# tree.net
KiCad netlist of a schematic drawn in EAGLE
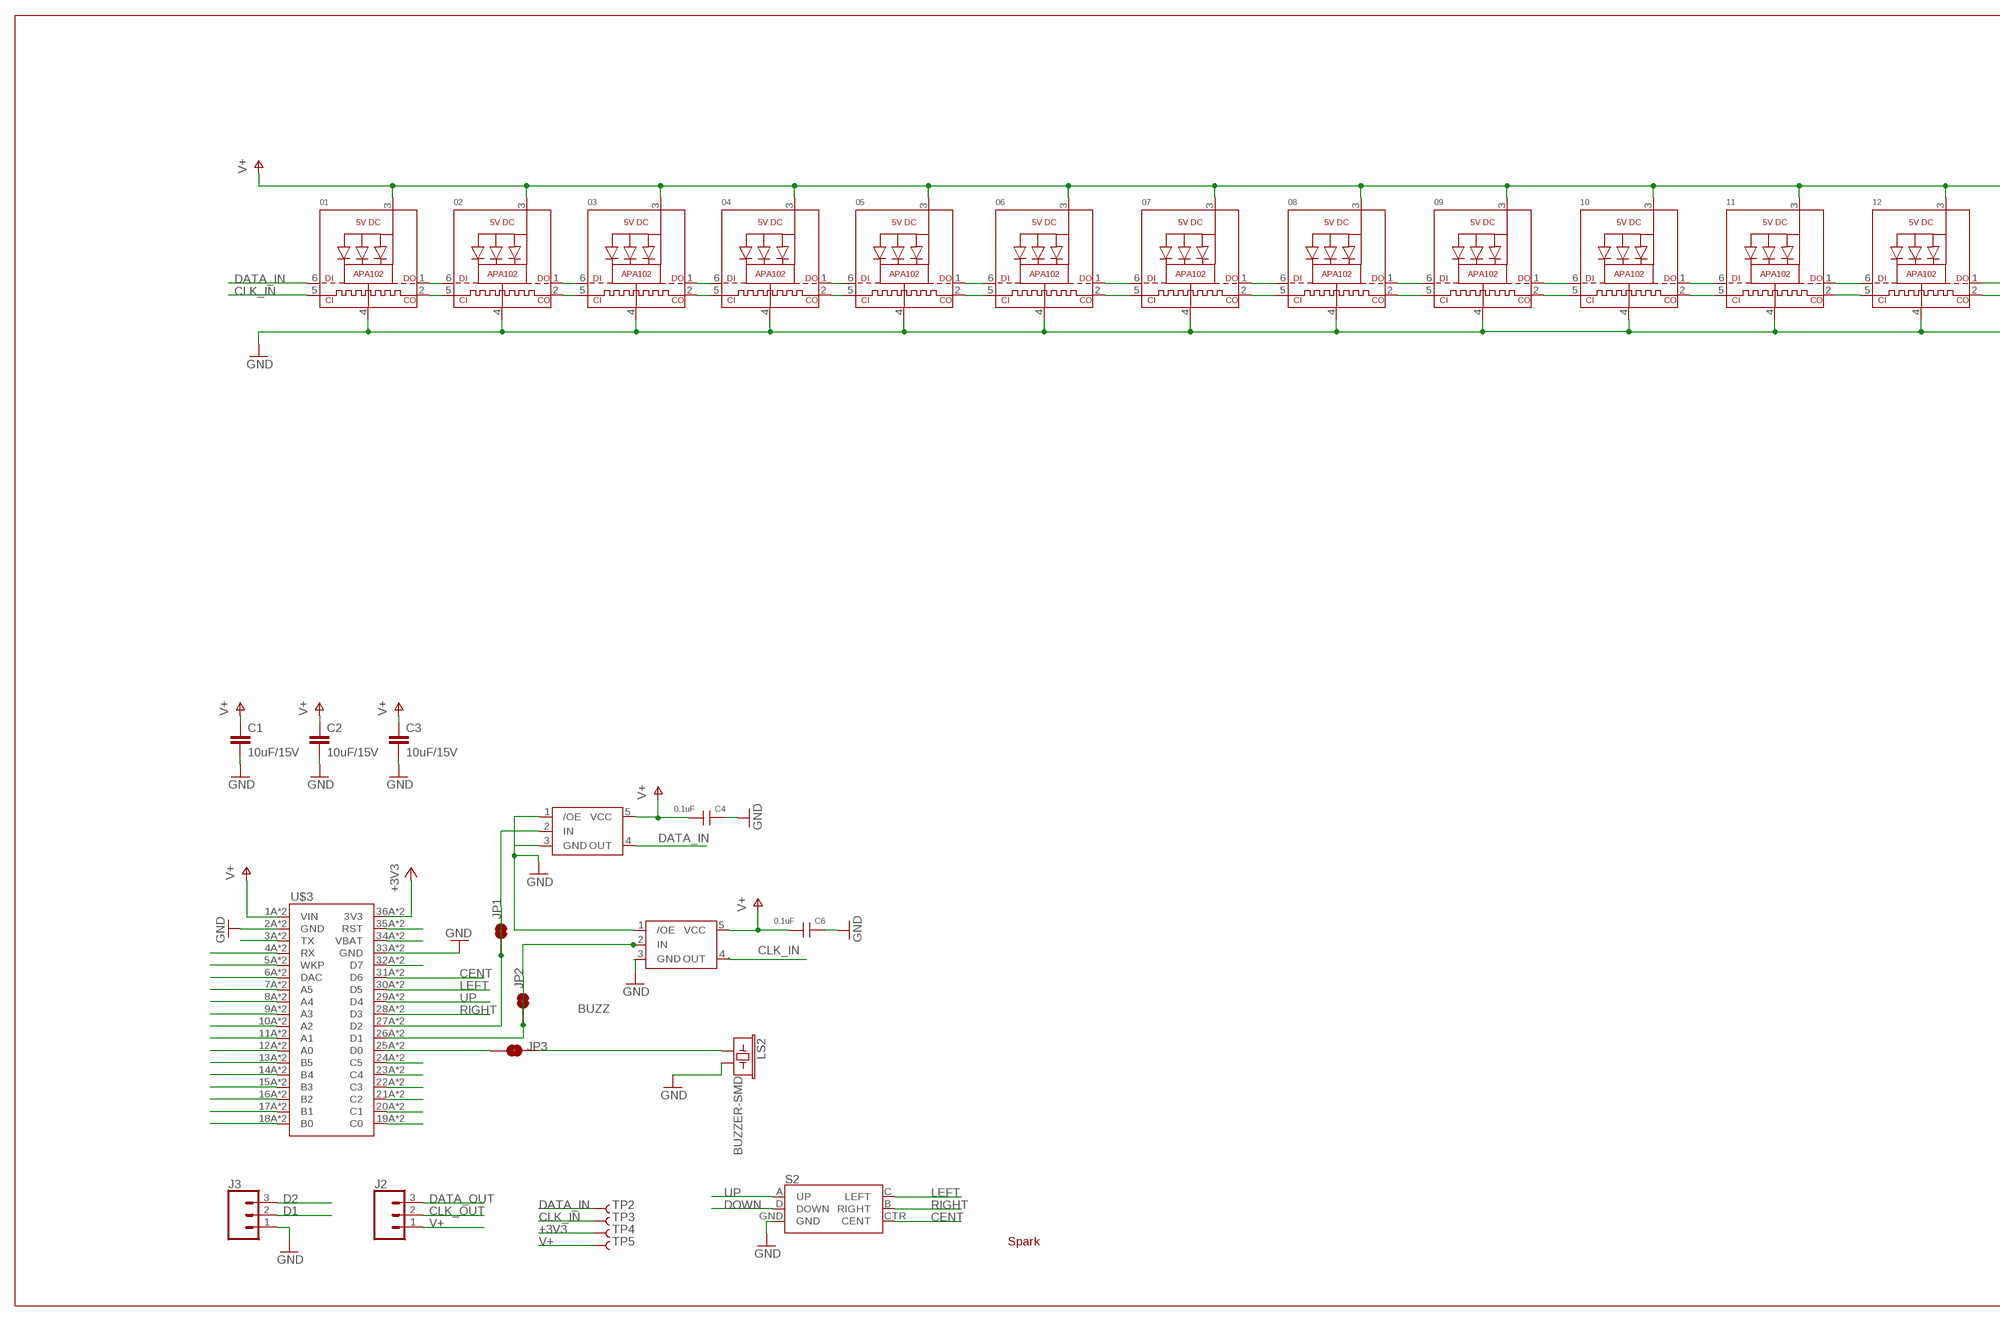
[diagram p0: schematic, sheet 1, part 1 of 3]
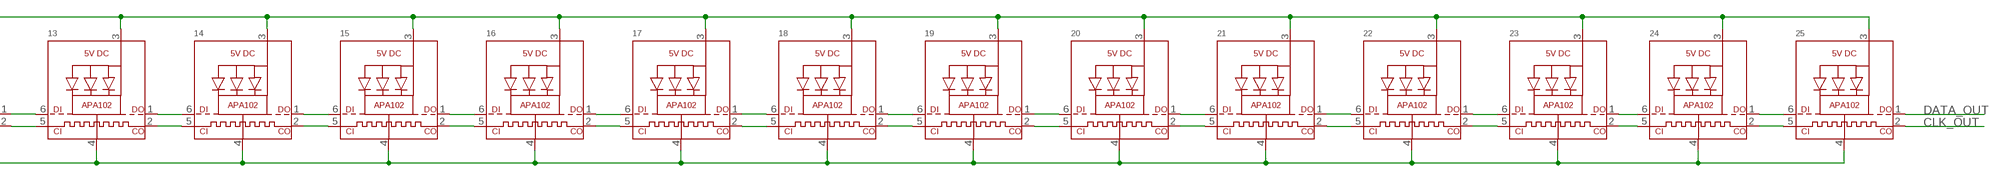
[diagram p1: schematic, sheet 1, part 2 of 3]
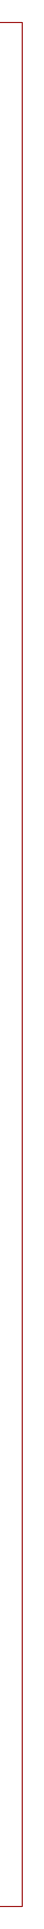
[diagram p2: schematic, sheet 1, part 3 of 3]

(export (version "E")
  (design (tool "Eeschema 10.0.6"))
  (components
    (comp (ref "01")
      (value "APA1022020")
      (footprint "eagle-import:APA102_2020")
      (libsource (lib "eagle-import") (part "APA1022020"))
    )
    (comp (ref "02")
      (value "APA1022020")
      (footprint "eagle-import:APA102_2020")
      (libsource (lib "eagle-import") (part "APA1022020"))
    )
    (comp (ref "03")
      (value "APA1022020")
      (footprint "eagle-import:APA102_2020")
      (libsource (lib "eagle-import") (part "APA1022020"))
    )
    (comp (ref "04")
      (value "APA1022020")
      (footprint "eagle-import:APA102_2020")
      (libsource (lib "eagle-import") (part "APA1022020"))
    )
    (comp (ref "05")
      (value "APA1022020")
      (footprint "eagle-import:APA102_2020")
      (libsource (lib "eagle-import") (part "APA1022020"))
    )
    (comp (ref "06")
      (value "APA1022020")
      (footprint "eagle-import:APA102_2020")
      (libsource (lib "eagle-import") (part "APA1022020"))
    )
    (comp (ref "07")
      (value "APA1022020")
      (footprint "eagle-import:APA102_2020")
      (libsource (lib "eagle-import") (part "APA1022020"))
    )
    (comp (ref "08")
      (value "APA1022020")
      (footprint "eagle-import:APA102_2020")
      (libsource (lib "eagle-import") (part "APA1022020"))
    )
    (comp (ref "09")
      (value "APA1022020")
      (footprint "eagle-import:APA102_2020")
      (libsource (lib "eagle-import") (part "APA1022020"))
    )
    (comp (ref "10")
      (value "APA1022020")
      (footprint "eagle-import:APA102_2020")
      (libsource (lib "eagle-import") (part "APA1022020"))
    )
    (comp (ref "11")
      (value "APA1022020")
      (footprint "eagle-import:APA102_2020")
      (libsource (lib "eagle-import") (part "APA1022020"))
    )
    (comp (ref "12")
      (value "APA1022020")
      (footprint "eagle-import:APA102_2020")
      (libsource (lib "eagle-import") (part "APA1022020"))
    )
    (comp (ref "13")
      (value "APA1022020")
      (footprint "eagle-import:APA102_2020")
      (libsource (lib "eagle-import") (part "APA1022020"))
    )
    (comp (ref "14")
      (value "APA1022020")
      (footprint "eagle-import:APA102_2020")
      (libsource (lib "eagle-import") (part "APA1022020"))
    )
    (comp (ref "15")
      (value "APA1022020")
      (footprint "eagle-import:APA102_2020")
      (libsource (lib "eagle-import") (part "APA1022020"))
    )
    (comp (ref "16")
      (value "APA1022020")
      (footprint "eagle-import:APA102_2020")
      (libsource (lib "eagle-import") (part "APA1022020"))
    )
    (comp (ref "17")
      (value "APA1022020")
      (footprint "eagle-import:APA102_2020")
      (libsource (lib "eagle-import") (part "APA1022020"))
    )
    (comp (ref "18")
      (value "APA1022020")
      (footprint "eagle-import:APA102_2020")
      (libsource (lib "eagle-import") (part "APA1022020"))
    )
    (comp (ref "19")
      (value "APA1022020")
      (footprint "eagle-import:APA102_2020")
      (libsource (lib "eagle-import") (part "APA1022020"))
    )
    (comp (ref "20")
      (value "APA1022020")
      (footprint "eagle-import:APA102_2020")
      (libsource (lib "eagle-import") (part "APA1022020"))
    )
    (comp (ref "21")
      (value "APA1022020")
      (footprint "eagle-import:APA102_2020")
      (libsource (lib "eagle-import") (part "APA1022020"))
    )
    (comp (ref "22")
      (value "APA1022020")
      (footprint "eagle-import:APA102_2020")
      (libsource (lib "eagle-import") (part "APA1022020"))
    )
    (comp (ref "23")
      (value "APA1022020")
      (footprint "eagle-import:APA102_2020")
      (libsource (lib "eagle-import") (part "APA1022020"))
    )
    (comp (ref "24")
      (value "APA1022020")
      (footprint "eagle-import:APA102_2020")
      (libsource (lib "eagle-import") (part "APA1022020"))
    )
    (comp (ref "25")
      (value "APA1022020")
      (footprint "eagle-import:APA102_2020")
      (libsource (lib "eagle-import") (part "APA1022020"))
    )
    (comp (ref "C1")
      (value "10uF/15V")
      (footprint "eagle-import:C0805K")
      (libsource (lib "eagle-import") (part "C-EUC0805K"))
    )
    (comp (ref "C2")
      (value "10uF/15V")
      (footprint "eagle-import:C0805K")
      (libsource (lib "eagle-import") (part "C-EUC0805K"))
    )
    (comp (ref "C3")
      (value "10uF/15V")
      (footprint "eagle-import:C0805K")
      (libsource (lib "eagle-import") (part "C-EUC0805K"))
    )
    (comp (ref "C4")
      (value "0.1uF")
      (footprint "eagle-import:C-0603A")
      (libsource (lib "eagle-import") (part "CAP0603A"))
    )
    (comp (ref "C6")
      (value "0.1uF")
      (footprint "eagle-import:C-0603A")
      (libsource (lib "eagle-import") (part "CAP0603A"))
    )
    (comp (ref "J2")
      (value "CONN_03")
      (footprint "eagle-import:1X03")
      (libsource (lib "eagle-import") (part "CONN_03"))
    )
    (comp (ref "J3")
      (value "CONN_03")
      (footprint "eagle-import:1X03")
      (libsource (lib "eagle-import") (part "CONN_03"))
    )
    (comp (ref "JP1")
      (value "JUMPER-SMT_2_NC_TRACE_NO-SILK")
      (footprint "eagle-import:SMT-JUMPER_2_NC_TRACE_NO-SILK")
      (libsource (lib "eagle-import") (part "JUMPER-SMT_2_NC_TRACE_NO-SILK"))
    )
    (comp (ref "JP2")
      (value "JUMPER-SMT_2_NC_TRACE_NO-SILK")
      (footprint "eagle-import:SMT-JUMPER_2_NC_TRACE_NO-SILK")
      (libsource (lib "eagle-import") (part "JUMPER-SMT_2_NC_TRACE_NO-SILK"))
    )
    (comp (ref "JP3")
      (value "JUMPER-SMT_2_NC_TRACE_NO-SILK")
      (footprint "eagle-import:SMT-JUMPER_2_NC_TRACE_NO-SILK")
      (libsource (lib "eagle-import") (part "JUMPER-SMT_2_NC_TRACE_NO-SILK"))
    )
    (comp (ref "LS2")
      (value "BUZZER-SMD")
      (footprint "eagle-import:BUZZER-CCV")
      (libsource (lib "eagle-import") (part "BUZZER-SMD"))
    )
    (comp (ref "S2")
      (value "JOYSTICK_MINI")
      (footprint "eagle-import:JOYSTICK_MINI")
      (libsource (lib "eagle-import") (part "JOYSTICK_MINI"))
    )
    (comp (ref "TP2")
      (value "TEST-POINT3")
      (footprint "eagle-import:PAD.03X.03")
      (libsource (lib "eagle-import") (part "TEST-POINT3"))
    )
    (comp (ref "TP3")
      (value "TEST-POINT3")
      (footprint "eagle-import:PAD.03X.03")
      (libsource (lib "eagle-import") (part "TEST-POINT3"))
    )
    (comp (ref "TP4")
      (value "TEST-POINT3")
      (footprint "eagle-import:PAD.03X.03")
      (libsource (lib "eagle-import") (part "TEST-POINT3"))
    )
    (comp (ref "TP5")
      (value "TEST-POINT3")
      (footprint "eagle-import:PAD.03X.03")
      (libsource (lib "eagle-import") (part "TEST-POINT3"))
    )
    (comp (ref "U$1")
      (value "SPARK_LOGO")
      (footprint "eagle-import:SPARK_LOGO_TSTOP")
      (libsource (lib "eagle-import") (part "SPARK_LOGO"))
    )
    (comp (ref "U$3")
      (value "ELECTRON_SMT")
      (footprint "eagle-import:ELECTRON_SMT")
      (libsource (lib "eagle-import") (part "ELECTRON_SMT"))
    )
    (comp (ref "U1")
      (value "NL17SZ125")
      (footprint "eagle-import:SOT-353")
      (libsource (lib "eagle-import") (part "NL17SZ125"))
    )
    (comp (ref "U2")
      (value "NL17SZ125")
      (footprint "eagle-import:SOT-353")
      (libsource (lib "eagle-import") (part "NL17SZ125"))
    )
  )
  (nets
    (net (code "1") (name "+3V3") (class "Default")
      (node (ref "TP4") (pin "P$1") (pinfunction "1_P$1") (pintype "bidirectional"))
      (node (ref "U$3") (pin "36A") (pinfunction "3V3_36A") (pintype "power_in"))
      (node (ref "U$3") (pin "36B") (pinfunction "3V3_36B") (pintype "power_in"))
    )
    (net (code "2") (name "/BUZZ") (class "Default")
      (node (ref "JP3") (pin "1") (pinfunction "1_1") (pintype "passive"))
      (node (ref "U$3") (pin "25A") (pinfunction "D0_25A") (pintype "bidirectional"))
      (node (ref "U$3") (pin "25B") (pinfunction "D0_25B") (pintype "bidirectional"))
    )
    (net (code "3") (name "/CENT") (class "Default")
      (node (ref "S2") (pin "CTR") (pinfunction "CENT_CTR") (pintype "bidirectional"))
      (node (ref "U$3") (pin "31A") (pinfunction "D6_31A") (pintype "bidirectional"))
      (node (ref "U$3") (pin "31B") (pinfunction "D6_31B") (pintype "bidirectional"))
    )
    (net (code "4") (name "/CLK_IN") (class "Default")
      (node (ref "01") (pin "5") (pinfunction "CKI_5") (pintype "input"))
      (node (ref "TP3") (pin "P$1") (pinfunction "1_P$1") (pintype "bidirectional"))
      (node (ref "U2") (pin "4") (pinfunction "OUT_4") (pintype "bidirectional"))
    )
    (net (code "5") (name "/CLK_OUT") (class "Default")
      (node (ref "25") (pin "2") (pinfunction "CKO_2") (pintype "output"))
      (node (ref "J2") (pin "2") (pinfunction "2_2") (pintype "passive"))
    )
    (net (code "6") (name "/D1") (class "Default")
      (node (ref "J3") (pin "2") (pinfunction "2_2") (pintype "passive"))
      (node (ref "JP2") (pin "1") (pinfunction "1_1") (pintype "passive"))
      (node (ref "JP2") (pin "2") (pinfunction "2_2") (pintype "passive"))
      (node (ref "U$3") (pin "26A") (pinfunction "D1_26A") (pintype "bidirectional"))
      (node (ref "U$3") (pin "26B") (pinfunction "D1_26B") (pintype "bidirectional"))
      (node (ref "U2") (pin "2") (pinfunction "IN_2") (pintype "bidirectional"))
    )
    (net (code "7") (name "/D2") (class "Default")
      (node (ref "J3") (pin "3") (pinfunction "3_3") (pintype "passive"))
      (node (ref "JP1") (pin "1") (pinfunction "1_1") (pintype "passive"))
      (node (ref "JP1") (pin "2") (pinfunction "2_2") (pintype "passive"))
      (node (ref "U$3") (pin "27A") (pinfunction "D2_27A") (pintype "bidirectional"))
      (node (ref "U$3") (pin "27B") (pinfunction "D2_27B") (pintype "bidirectional"))
      (node (ref "U1") (pin "2") (pinfunction "IN_2") (pintype "bidirectional"))
    )
    (net (code "8") (name "/DATA_IN") (class "Default")
      (node (ref "01") (pin "6") (pinfunction "DI_6") (pintype "input"))
      (node (ref "TP2") (pin "P$1") (pinfunction "1_P$1") (pintype "bidirectional"))
      (node (ref "U1") (pin "4") (pinfunction "OUT_4") (pintype "bidirectional"))
    )
    (net (code "9") (name "/DATA_OUT") (class "Default")
      (node (ref "25") (pin "1") (pinfunction "DO_1") (pintype "output"))
      (node (ref "J2") (pin "3") (pinfunction "3_3") (pintype "passive"))
    )
    (net (code "10") (name "/DOWN") (class "Default")
      (node (ref "S2") (pin "D") (pinfunction "DOWN_D") (pintype "bidirectional"))
      (node (ref "U$3") (pin "12A") (pinfunction "A0_12A") (pintype "bidirectional"))
      (node (ref "U$3") (pin "12B") (pinfunction "A0_12B") (pintype "bidirectional"))
    )
    (net (code "11") (name "/LEFT") (class "Default")
      (node (ref "S2") (pin "C") (pinfunction "LEFT_C") (pintype "bidirectional"))
      (node (ref "U$3") (pin "30A") (pinfunction "D5_30A") (pintype "bidirectional"))
      (node (ref "U$3") (pin "30B") (pinfunction "D5_30B") (pintype "bidirectional"))
    )
    (net (code "12") (name "/RIGHT") (class "Default")
      (node (ref "S2") (pin "B") (pinfunction "RIGHT_B") (pintype "bidirectional"))
      (node (ref "U$3") (pin "28A") (pinfunction "D3_28A") (pintype "bidirectional"))
      (node (ref "U$3") (pin "28B") (pinfunction "D3_28B") (pintype "bidirectional"))
    )
    (net (code "13") (name "/UP") (class "Default")
      (node (ref "S2") (pin "A") (pinfunction "UP_A") (pintype "bidirectional"))
      (node (ref "U$3") (pin "29A") (pinfunction "D4_29A") (pintype "bidirectional"))
      (node (ref "U$3") (pin "29B") (pinfunction "D4_29B") (pintype "bidirectional"))
    )
    (net (code "14") (name "GND") (class "Default")
      (node (ref "01") (pin "4") (pinfunction "GND_4") (pintype "power_in"))
      (node (ref "02") (pin "4") (pinfunction "GND_4") (pintype "power_in"))
      (node (ref "03") (pin "4") (pinfunction "GND_4") (pintype "power_in"))
      (node (ref "04") (pin "4") (pinfunction "GND_4") (pintype "power_in"))
      (node (ref "05") (pin "4") (pinfunction "GND_4") (pintype "power_in"))
      (node (ref "06") (pin "4") (pinfunction "GND_4") (pintype "power_in"))
      (node (ref "07") (pin "4") (pinfunction "GND_4") (pintype "power_in"))
      (node (ref "08") (pin "4") (pinfunction "GND_4") (pintype "power_in"))
      (node (ref "09") (pin "4") (pinfunction "GND_4") (pintype "power_in"))
      (node (ref "10") (pin "4") (pinfunction "GND_4") (pintype "power_in"))
      (node (ref "11") (pin "4") (pinfunction "GND_4") (pintype "power_in"))
      (node (ref "12") (pin "4") (pinfunction "GND_4") (pintype "power_in"))
      (node (ref "13") (pin "4") (pinfunction "GND_4") (pintype "power_in"))
      (node (ref "14") (pin "4") (pinfunction "GND_4") (pintype "power_in"))
      (node (ref "15") (pin "4") (pinfunction "GND_4") (pintype "power_in"))
      (node (ref "16") (pin "4") (pinfunction "GND_4") (pintype "power_in"))
      (node (ref "17") (pin "4") (pinfunction "GND_4") (pintype "power_in"))
      (node (ref "18") (pin "4") (pinfunction "GND_4") (pintype "power_in"))
      (node (ref "19") (pin "4") (pinfunction "GND_4") (pintype "power_in"))
      (node (ref "20") (pin "4") (pinfunction "GND_4") (pintype "power_in"))
      (node (ref "21") (pin "4") (pinfunction "GND_4") (pintype "power_in"))
      (node (ref "22") (pin "4") (pinfunction "GND_4") (pintype "power_in"))
      (node (ref "23") (pin "4") (pinfunction "GND_4") (pintype "power_in"))
      (node (ref "24") (pin "4") (pinfunction "GND_4") (pintype "power_in"))
      (node (ref "25") (pin "4") (pinfunction "GND_4") (pintype "power_in"))
      (node (ref "C1") (pin "2") (pinfunction "2_2") (pintype "passive"))
      (node (ref "C2") (pin "2") (pinfunction "2_2") (pintype "passive"))
      (node (ref "C3") (pin "2") (pinfunction "2_2") (pintype "passive"))
      (node (ref "C4") (pin "2") (pinfunction "2_2") (pintype "bidirectional"))
      (node (ref "C6") (pin "2") (pinfunction "2_2") (pintype "bidirectional"))
      (node (ref "J3") (pin "1") (pinfunction "1_1") (pintype "passive"))
      (node (ref "LS2") (pin "-") (pinfunction "2_-") (pintype "passive"))
      (node (ref "S2") (pin "GND") (pinfunction "GND_GND") (pintype "bidirectional"))
      (node (ref "U$3") (pin "2A") (pinfunction "GND_2A") (pintype "power_in"))
      (node (ref "U$3") (pin "2B") (pinfunction "GND_2B") (pintype "power_in"))
      (node (ref "U$3") (pin "33A") (pinfunction "GND_33A") (pintype "power_in"))
      (node (ref "U$3") (pin "33B") (pinfunction "GND_33B") (pintype "power_in"))
      (node (ref "U1") (pin "1") (pinfunction "/OE_1") (pintype "bidirectional"))
      (node (ref "U1") (pin "3") (pinfunction "GND_3") (pintype "bidirectional"))
      (node (ref "U2") (pin "1") (pinfunction "/OE_1") (pintype "bidirectional"))
      (node (ref "U2") (pin "3") (pinfunction "GND_3") (pintype "bidirectional"))
    )
    (net (code "15") (name "Net-(01-CKO)") (class "Default")
      (node (ref "01") (pin "2") (pinfunction "CKO_2") (pintype "output"))
      (node (ref "02") (pin "5") (pinfunction "CKI_5") (pintype "input"))
    )
    (net (code "16") (name "Net-(01-DO)") (class "Default")
      (node (ref "01") (pin "1") (pinfunction "DO_1") (pintype "output"))
      (node (ref "02") (pin "6") (pinfunction "DI_6") (pintype "input"))
    )
    (net (code "17") (name "Net-(02-CKO)") (class "Default")
      (node (ref "02") (pin "2") (pinfunction "CKO_2") (pintype "output"))
      (node (ref "03") (pin "5") (pinfunction "CKI_5") (pintype "input"))
    )
    (net (code "18") (name "Net-(02-DO)") (class "Default")
      (node (ref "02") (pin "1") (pinfunction "DO_1") (pintype "output"))
      (node (ref "03") (pin "6") (pinfunction "DI_6") (pintype "input"))
    )
    (net (code "19") (name "Net-(03-CKO)") (class "Default")
      (node (ref "03") (pin "2") (pinfunction "CKO_2") (pintype "output"))
      (node (ref "04") (pin "5") (pinfunction "CKI_5") (pintype "input"))
    )
    (net (code "20") (name "Net-(03-DO)") (class "Default")
      (node (ref "03") (pin "1") (pinfunction "DO_1") (pintype "output"))
      (node (ref "04") (pin "6") (pinfunction "DI_6") (pintype "input"))
    )
    (net (code "21") (name "Net-(04-CKO)") (class "Default")
      (node (ref "04") (pin "2") (pinfunction "CKO_2") (pintype "output"))
      (node (ref "05") (pin "5") (pinfunction "CKI_5") (pintype "input"))
    )
    (net (code "22") (name "Net-(04-DO)") (class "Default")
      (node (ref "04") (pin "1") (pinfunction "DO_1") (pintype "output"))
      (node (ref "05") (pin "6") (pinfunction "DI_6") (pintype "input"))
    )
    (net (code "23") (name "Net-(05-CKO)") (class "Default")
      (node (ref "05") (pin "2") (pinfunction "CKO_2") (pintype "output"))
      (node (ref "06") (pin "5") (pinfunction "CKI_5") (pintype "input"))
    )
    (net (code "24") (name "Net-(05-DO)") (class "Default")
      (node (ref "05") (pin "1") (pinfunction "DO_1") (pintype "output"))
      (node (ref "06") (pin "6") (pinfunction "DI_6") (pintype "input"))
    )
    (net (code "25") (name "Net-(06-CKO)") (class "Default")
      (node (ref "06") (pin "2") (pinfunction "CKO_2") (pintype "output"))
      (node (ref "07") (pin "5") (pinfunction "CKI_5") (pintype "input"))
    )
    (net (code "26") (name "Net-(06-DO)") (class "Default")
      (node (ref "06") (pin "1") (pinfunction "DO_1") (pintype "output"))
      (node (ref "07") (pin "6") (pinfunction "DI_6") (pintype "input"))
    )
    (net (code "27") (name "Net-(07-CKO)") (class "Default")
      (node (ref "07") (pin "2") (pinfunction "CKO_2") (pintype "output"))
      (node (ref "08") (pin "5") (pinfunction "CKI_5") (pintype "input"))
    )
    (net (code "28") (name "Net-(07-DO)") (class "Default")
      (node (ref "07") (pin "1") (pinfunction "DO_1") (pintype "output"))
      (node (ref "08") (pin "6") (pinfunction "DI_6") (pintype "input"))
    )
    (net (code "29") (name "Net-(08-CKO)") (class "Default")
      (node (ref "08") (pin "2") (pinfunction "CKO_2") (pintype "output"))
      (node (ref "09") (pin "5") (pinfunction "CKI_5") (pintype "input"))
    )
    (net (code "30") (name "Net-(08-DO)") (class "Default")
      (node (ref "08") (pin "1") (pinfunction "DO_1") (pintype "output"))
      (node (ref "09") (pin "6") (pinfunction "DI_6") (pintype "input"))
    )
    (net (code "31") (name "Net-(09-CKO)") (class "Default")
      (node (ref "09") (pin "2") (pinfunction "CKO_2") (pintype "output"))
      (node (ref "10") (pin "5") (pinfunction "CKI_5") (pintype "input"))
    )
    (net (code "32") (name "Net-(09-DO)") (class "Default")
      (node (ref "09") (pin "1") (pinfunction "DO_1") (pintype "output"))
      (node (ref "10") (pin "6") (pinfunction "DI_6") (pintype "input"))
    )
    (net (code "33") (name "Net-(10-CKO)") (class "Default")
      (node (ref "10") (pin "2") (pinfunction "CKO_2") (pintype "output"))
      (node (ref "11") (pin "5") (pinfunction "CKI_5") (pintype "input"))
    )
    (net (code "34") (name "Net-(10-DO)") (class "Default")
      (node (ref "10") (pin "1") (pinfunction "DO_1") (pintype "output"))
      (node (ref "11") (pin "6") (pinfunction "DI_6") (pintype "input"))
    )
    (net (code "35") (name "Net-(11-CKO)") (class "Default")
      (node (ref "11") (pin "2") (pinfunction "CKO_2") (pintype "output"))
      (node (ref "12") (pin "5") (pinfunction "CKI_5") (pintype "input"))
    )
    (net (code "36") (name "Net-(11-DO)") (class "Default")
      (node (ref "11") (pin "1") (pinfunction "DO_1") (pintype "output"))
      (node (ref "12") (pin "6") (pinfunction "DI_6") (pintype "input"))
    )
    (net (code "37") (name "Net-(12-CKO)") (class "Default")
      (node (ref "12") (pin "2") (pinfunction "CKO_2") (pintype "output"))
      (node (ref "13") (pin "5") (pinfunction "CKI_5") (pintype "input"))
    )
    (net (code "38") (name "Net-(12-DO)") (class "Default")
      (node (ref "12") (pin "1") (pinfunction "DO_1") (pintype "output"))
      (node (ref "13") (pin "6") (pinfunction "DI_6") (pintype "input"))
    )
    (net (code "39") (name "Net-(13-CKO)") (class "Default")
      (node (ref "13") (pin "2") (pinfunction "CKO_2") (pintype "output"))
      (node (ref "14") (pin "5") (pinfunction "CKI_5") (pintype "input"))
    )
    (net (code "40") (name "Net-(13-DO)") (class "Default")
      (node (ref "13") (pin "1") (pinfunction "DO_1") (pintype "output"))
      (node (ref "14") (pin "6") (pinfunction "DI_6") (pintype "input"))
    )
    (net (code "41") (name "Net-(14-CKO)") (class "Default")
      (node (ref "14") (pin "2") (pinfunction "CKO_2") (pintype "output"))
      (node (ref "15") (pin "5") (pinfunction "CKI_5") (pintype "input"))
    )
    (net (code "42") (name "Net-(14-DO)") (class "Default")
      (node (ref "14") (pin "1") (pinfunction "DO_1") (pintype "output"))
      (node (ref "15") (pin "6") (pinfunction "DI_6") (pintype "input"))
    )
    (net (code "43") (name "Net-(15-CKO)") (class "Default")
      (node (ref "15") (pin "2") (pinfunction "CKO_2") (pintype "output"))
      (node (ref "16") (pin "5") (pinfunction "CKI_5") (pintype "input"))
    )
    (net (code "44") (name "Net-(15-DO)") (class "Default")
      (node (ref "15") (pin "1") (pinfunction "DO_1") (pintype "output"))
      (node (ref "16") (pin "6") (pinfunction "DI_6") (pintype "input"))
    )
    (net (code "45") (name "Net-(16-CKO)") (class "Default")
      (node (ref "16") (pin "2") (pinfunction "CKO_2") (pintype "output"))
      (node (ref "17") (pin "5") (pinfunction "CKI_5") (pintype "input"))
    )
    (net (code "46") (name "Net-(16-DO)") (class "Default")
      (node (ref "16") (pin "1") (pinfunction "DO_1") (pintype "output"))
      (node (ref "17") (pin "6") (pinfunction "DI_6") (pintype "input"))
    )
    (net (code "47") (name "Net-(17-CKO)") (class "Default")
      (node (ref "17") (pin "2") (pinfunction "CKO_2") (pintype "output"))
      (node (ref "18") (pin "5") (pinfunction "CKI_5") (pintype "input"))
    )
    (net (code "48") (name "Net-(17-DO)") (class "Default")
      (node (ref "17") (pin "1") (pinfunction "DO_1") (pintype "output"))
      (node (ref "18") (pin "6") (pinfunction "DI_6") (pintype "input"))
    )
    (net (code "49") (name "Net-(18-CKO)") (class "Default")
      (node (ref "18") (pin "2") (pinfunction "CKO_2") (pintype "output"))
      (node (ref "19") (pin "5") (pinfunction "CKI_5") (pintype "input"))
    )
    (net (code "50") (name "Net-(18-DO)") (class "Default")
      (node (ref "18") (pin "1") (pinfunction "DO_1") (pintype "output"))
      (node (ref "19") (pin "6") (pinfunction "DI_6") (pintype "input"))
    )
    (net (code "51") (name "Net-(19-CKO)") (class "Default")
      (node (ref "19") (pin "2") (pinfunction "CKO_2") (pintype "output"))
      (node (ref "20") (pin "5") (pinfunction "CKI_5") (pintype "input"))
    )
    (net (code "52") (name "Net-(19-DO)") (class "Default")
      (node (ref "19") (pin "1") (pinfunction "DO_1") (pintype "output"))
      (node (ref "20") (pin "6") (pinfunction "DI_6") (pintype "input"))
    )
    (net (code "53") (name "Net-(20-CKO)") (class "Default")
      (node (ref "20") (pin "2") (pinfunction "CKO_2") (pintype "output"))
      (node (ref "21") (pin "5") (pinfunction "CKI_5") (pintype "input"))
    )
    (net (code "54") (name "Net-(20-DO)") (class "Default")
      (node (ref "20") (pin "1") (pinfunction "DO_1") (pintype "output"))
      (node (ref "21") (pin "6") (pinfunction "DI_6") (pintype "input"))
    )
    (net (code "55") (name "Net-(21-CKO)") (class "Default")
      (node (ref "21") (pin "2") (pinfunction "CKO_2") (pintype "output"))
      (node (ref "22") (pin "5") (pinfunction "CKI_5") (pintype "input"))
    )
    (net (code "56") (name "Net-(21-DO)") (class "Default")
      (node (ref "21") (pin "1") (pinfunction "DO_1") (pintype "output"))
      (node (ref "22") (pin "6") (pinfunction "DI_6") (pintype "input"))
    )
    (net (code "57") (name "Net-(22-CKO)") (class "Default")
      (node (ref "22") (pin "2") (pinfunction "CKO_2") (pintype "output"))
      (node (ref "23") (pin "5") (pinfunction "CKI_5") (pintype "input"))
    )
    (net (code "58") (name "Net-(22-DO)") (class "Default")
      (node (ref "22") (pin "1") (pinfunction "DO_1") (pintype "output"))
      (node (ref "23") (pin "6") (pinfunction "DI_6") (pintype "input"))
    )
    (net (code "59") (name "Net-(23-CKO)") (class "Default")
      (node (ref "23") (pin "2") (pinfunction "CKO_2") (pintype "output"))
      (node (ref "24") (pin "5") (pinfunction "CKI_5") (pintype "input"))
    )
    (net (code "60") (name "Net-(23-DO)") (class "Default")
      (node (ref "23") (pin "1") (pinfunction "DO_1") (pintype "output"))
      (node (ref "24") (pin "6") (pinfunction "DI_6") (pintype "input"))
    )
    (net (code "61") (name "Net-(24-CKO)") (class "Default")
      (node (ref "24") (pin "2") (pinfunction "CKO_2") (pintype "output"))
      (node (ref "25") (pin "5") (pinfunction "CKI_5") (pintype "input"))
    )
    (net (code "62") (name "Net-(24-DO)") (class "Default")
      (node (ref "24") (pin "1") (pinfunction "DO_1") (pintype "output"))
      (node (ref "25") (pin "6") (pinfunction "DI_6") (pintype "input"))
    )
    (net (code "63") (name "Net-(LS2-1)") (class "Default")
      (node (ref "JP3") (pin "2") (pinfunction "2_2") (pintype "passive"))
      (node (ref "LS2") (pin "+") (pinfunction "1_+") (pintype "passive"))
    )
    (net (code "64") (name "Net-(U$3-A1-Pad11A)") (class "Default")
      (node (ref "U$3") (pin "11A") (pinfunction "A1_11A") (pintype "bidirectional"))
      (node (ref "U$3") (pin "11B") (pinfunction "A1_11B") (pintype "bidirectional"))
    )
    (net (code "65") (name "Net-(U$3-A2-Pad10A)") (class "Default")
      (node (ref "U$3") (pin "10A") (pinfunction "A2_10A") (pintype "bidirectional"))
      (node (ref "U$3") (pin "10B") (pinfunction "A2_10B") (pintype "bidirectional"))
    )
    (net (code "66") (name "Net-(U$3-A3-Pad9A)") (class "Default")
      (node (ref "U$3") (pin "9A") (pinfunction "A3_9A") (pintype "bidirectional"))
      (node (ref "U$3") (pin "9B") (pinfunction "A3_9B") (pintype "bidirectional"))
    )
    (net (code "67") (name "Net-(U$3-A4-Pad8A)") (class "Default")
      (node (ref "U$3") (pin "8A") (pinfunction "A4_8A") (pintype "bidirectional"))
      (node (ref "U$3") (pin "8B") (pinfunction "A4_8B") (pintype "bidirectional"))
    )
    (net (code "68") (name "Net-(U$3-A5-Pad7A)") (class "Default")
      (node (ref "U$3") (pin "7A") (pinfunction "A5_7A") (pintype "bidirectional"))
      (node (ref "U$3") (pin "7B") (pinfunction "A5_7B") (pintype "bidirectional"))
    )
    (net (code "69") (name "Net-(U$3-B0-Pad18A)") (class "Default")
      (node (ref "U$3") (pin "18A") (pinfunction "B0_18A") (pintype "bidirectional"))
      (node (ref "U$3") (pin "18B") (pinfunction "B0_18B") (pintype "bidirectional"))
    )
    (net (code "70") (name "Net-(U$3-B1-Pad17A)") (class "Default")
      (node (ref "U$3") (pin "17A") (pinfunction "B1_17A") (pintype "bidirectional"))
      (node (ref "U$3") (pin "17B") (pinfunction "B1_17B") (pintype "bidirectional"))
    )
    (net (code "71") (name "Net-(U$3-B2-Pad16A)") (class "Default")
      (node (ref "U$3") (pin "16A") (pinfunction "B2_16A") (pintype "bidirectional"))
      (node (ref "U$3") (pin "16B") (pinfunction "B2_16B") (pintype "bidirectional"))
    )
    (net (code "72") (name "Net-(U$3-B3-Pad15A)") (class "Default")
      (node (ref "U$3") (pin "15A") (pinfunction "B3_15A") (pintype "bidirectional"))
      (node (ref "U$3") (pin "15B") (pinfunction "B3_15B") (pintype "bidirectional"))
    )
    (net (code "73") (name "Net-(U$3-B4-Pad14A)") (class "Default")
      (node (ref "U$3") (pin "14A") (pinfunction "B4_14A") (pintype "bidirectional"))
      (node (ref "U$3") (pin "14B") (pinfunction "B4_14B") (pintype "bidirectional"))
    )
    (net (code "74") (name "Net-(U$3-B5-Pad13A)") (class "Default")
      (node (ref "U$3") (pin "13A") (pinfunction "B5_13A") (pintype "bidirectional"))
      (node (ref "U$3") (pin "13B") (pinfunction "B5_13B") (pintype "bidirectional"))
    )
    (net (code "75") (name "Net-(U$3-C0-Pad19A)") (class "Default")
      (node (ref "U$3") (pin "19A") (pinfunction "C0_19A") (pintype "bidirectional"))
      (node (ref "U$3") (pin "19B") (pinfunction "C0_19B") (pintype "bidirectional"))
    )
    (net (code "76") (name "Net-(U$3-C1-Pad20A)") (class "Default")
      (node (ref "U$3") (pin "20A") (pinfunction "C1_20A") (pintype "bidirectional"))
      (node (ref "U$3") (pin "20B") (pinfunction "C1_20B") (pintype "bidirectional"))
    )
    (net (code "77") (name "Net-(U$3-C2-Pad21A)") (class "Default")
      (node (ref "U$3") (pin "21A") (pinfunction "C2_21A") (pintype "bidirectional"))
      (node (ref "U$3") (pin "21B") (pinfunction "C2_21B") (pintype "bidirectional"))
    )
    (net (code "78") (name "Net-(U$3-C3-Pad22A)") (class "Default")
      (node (ref "U$3") (pin "22A") (pinfunction "C3_22A") (pintype "bidirectional"))
      (node (ref "U$3") (pin "22B") (pinfunction "C3_22B") (pintype "bidirectional"))
    )
    (net (code "79") (name "Net-(U$3-C4-Pad23A)") (class "Default")
      (node (ref "U$3") (pin "23A") (pinfunction "C4_23A") (pintype "bidirectional"))
      (node (ref "U$3") (pin "23B") (pinfunction "C4_23B") (pintype "bidirectional"))
    )
    (net (code "80") (name "Net-(U$3-C5-Pad24A)") (class "Default")
      (node (ref "U$3") (pin "24A") (pinfunction "C5_24A") (pintype "bidirectional"))
      (node (ref "U$3") (pin "24B") (pinfunction "C5_24B") (pintype "bidirectional"))
    )
    (net (code "81") (name "Net-(U$3-D7-Pad32A)") (class "Default")
      (node (ref "U$3") (pin "32A") (pinfunction "D7_32A") (pintype "bidirectional"))
      (node (ref "U$3") (pin "32B") (pinfunction "D7_32B") (pintype "bidirectional"))
    )
    (net (code "82") (name "Net-(U$3-DAC-Pad6A)") (class "Default")
      (node (ref "U$3") (pin "6A") (pinfunction "DAC_6A") (pintype "bidirectional"))
      (node (ref "U$3") (pin "6B") (pinfunction "DAC_6B") (pintype "bidirectional"))
    )
    (net (code "83") (name "Net-(U$3-RST-Pad35A)") (class "Default")
      (node (ref "U$3") (pin "35A") (pinfunction "RST_35A") (pintype "bidirectional"))
      (node (ref "U$3") (pin "35B") (pinfunction "RST_35B") (pintype "bidirectional"))
    )
    (net (code "84") (name "Net-(U$3-RX-Pad4A)") (class "Default")
      (node (ref "U$3") (pin "4A") (pinfunction "RX_4A") (pintype "bidirectional"))
      (node (ref "U$3") (pin "4B") (pinfunction "RX_4B") (pintype "bidirectional"))
    )
    (net (code "85") (name "Net-(U$3-TX-Pad3A)") (class "Default")
      (node (ref "U$3") (pin "3A") (pinfunction "TX_3A") (pintype "bidirectional"))
      (node (ref "U$3") (pin "3B") (pinfunction "TX_3B") (pintype "bidirectional"))
    )
    (net (code "86") (name "Net-(U$3-VBAT-Pad34A)") (class "Default")
      (node (ref "U$3") (pin "34A") (pinfunction "VBAT_34A") (pintype "passive"))
      (node (ref "U$3") (pin "34B") (pinfunction "VBAT_34B") (pintype "passive"))
    )
    (net (code "87") (name "Net-(U$3-WKP-Pad5A)") (class "Default")
      (node (ref "U$3") (pin "5A") (pinfunction "WKP_5A") (pintype "bidirectional"))
      (node (ref "U$3") (pin "5B") (pinfunction "WKP_5B") (pintype "bidirectional"))
    )
    (net (code "88") (name "V+") (class "Default")
      (node (ref "01") (pin "3") (pinfunction "VDD_3") (pintype "power_in"))
      (node (ref "02") (pin "3") (pinfunction "VDD_3") (pintype "power_in"))
      (node (ref "03") (pin "3") (pinfunction "VDD_3") (pintype "power_in"))
      (node (ref "04") (pin "3") (pinfunction "VDD_3") (pintype "power_in"))
      (node (ref "05") (pin "3") (pinfunction "VDD_3") (pintype "power_in"))
      (node (ref "06") (pin "3") (pinfunction "VDD_3") (pintype "power_in"))
      (node (ref "07") (pin "3") (pinfunction "VDD_3") (pintype "power_in"))
      (node (ref "08") (pin "3") (pinfunction "VDD_3") (pintype "power_in"))
      (node (ref "09") (pin "3") (pinfunction "VDD_3") (pintype "power_in"))
      (node (ref "10") (pin "3") (pinfunction "VDD_3") (pintype "power_in"))
      (node (ref "11") (pin "3") (pinfunction "VDD_3") (pintype "power_in"))
      (node (ref "12") (pin "3") (pinfunction "VDD_3") (pintype "power_in"))
      (node (ref "13") (pin "3") (pinfunction "VDD_3") (pintype "power_in"))
      (node (ref "14") (pin "3") (pinfunction "VDD_3") (pintype "power_in"))
      (node (ref "15") (pin "3") (pinfunction "VDD_3") (pintype "power_in"))
      (node (ref "16") (pin "3") (pinfunction "VDD_3") (pintype "power_in"))
      (node (ref "17") (pin "3") (pinfunction "VDD_3") (pintype "power_in"))
      (node (ref "18") (pin "3") (pinfunction "VDD_3") (pintype "power_in"))
      (node (ref "19") (pin "3") (pinfunction "VDD_3") (pintype "power_in"))
      (node (ref "20") (pin "3") (pinfunction "VDD_3") (pintype "power_in"))
      (node (ref "21") (pin "3") (pinfunction "VDD_3") (pintype "power_in"))
      (node (ref "22") (pin "3") (pinfunction "VDD_3") (pintype "power_in"))
      (node (ref "23") (pin "3") (pinfunction "VDD_3") (pintype "power_in"))
      (node (ref "24") (pin "3") (pinfunction "VDD_3") (pintype "power_in"))
      (node (ref "25") (pin "3") (pinfunction "VDD_3") (pintype "power_in"))
      (node (ref "C1") (pin "1") (pinfunction "1_1") (pintype "passive"))
      (node (ref "C2") (pin "1") (pinfunction "1_1") (pintype "passive"))
      (node (ref "C3") (pin "1") (pinfunction "1_1") (pintype "passive"))
      (node (ref "C4") (pin "1") (pinfunction "1_1") (pintype "bidirectional"))
      (node (ref "C6") (pin "1") (pinfunction "1_1") (pintype "bidirectional"))
      (node (ref "J2") (pin "1") (pinfunction "1_1") (pintype "passive"))
      (node (ref "TP5") (pin "P$1") (pinfunction "1_P$1") (pintype "bidirectional"))
      (node (ref "U$3") (pin "1A") (pinfunction "VIN_1A") (pintype "power_in"))
      (node (ref "U$3") (pin "1B") (pinfunction "VIN_1B") (pintype "power_in"))
      (node (ref "U1") (pin "5") (pinfunction "VCC_5") (pintype "bidirectional"))
      (node (ref "U2") (pin "5") (pinfunction "VCC_5") (pintype "bidirectional"))
    )
  )
)
